# Sheet2-bms.net
KiCad netlist of a schematic drawn in Altium Designer
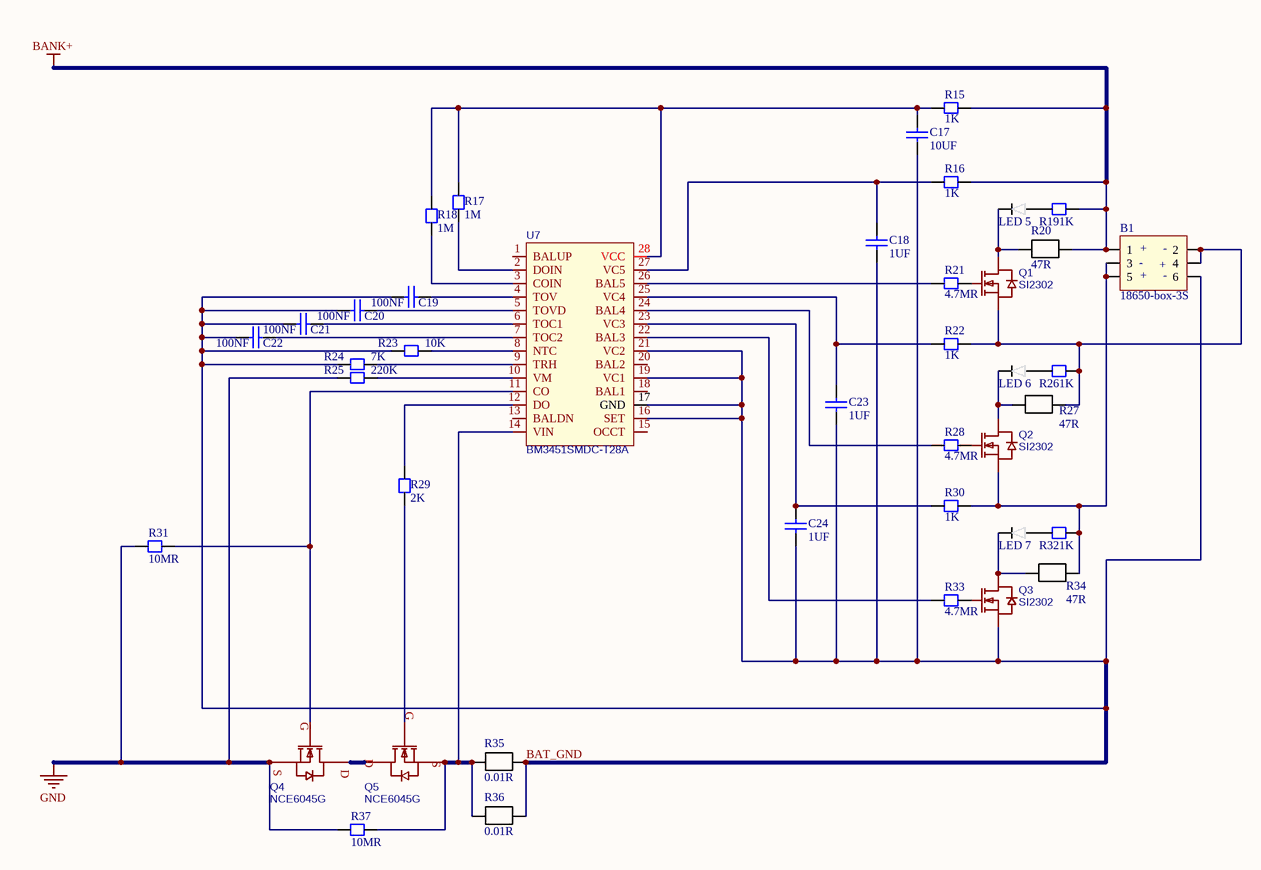
[diagram p0: Sheet2-bms.SchDoc]

(export (version "E")
  (design (tool "Eeschema 10.0.6"))
  (components
    (comp (ref "B1")
      (value "18650-box-3S")
      (footprint "BAT-SMD_BH-18650-B5BA016")
      (description "18650贴片电池盒")
      (libsource (lib "power-chip") (part "18650-box-3S"))
    )
    (comp (ref "C17")
      (value "10UF")
      (footprint "CC1608-0603")
      (description "0603封装的电容")
      (fields (field (name "PUBLISHER") "Altium Limited"))
      (libsource (lib "base") (part "Cap Chip 0603"))
    )
    (comp (ref "C18")
      (value "1UF")
      (footprint "CC1608-0603")
      (description "0603封装的电容")
      (fields (field (name "PUBLISHER") "Altium Limited"))
      (libsource (lib "base") (part "Cap Chip 0603"))
    )
    (comp (ref "C19")
      (value "100NF")
      (footprint "CC1608-0603")
      (description "0603封装的电容")
      (fields (field (name "PUBLISHER") "Altium Limited"))
      (libsource (lib "base") (part "Cap Chip 0603"))
    )
    (comp (ref "C20")
      (value "100NF")
      (footprint "CC1608-0603")
      (description "0603封装的电容")
      (fields (field (name "PUBLISHER") "Altium Limited"))
      (libsource (lib "base") (part "Cap Chip 0603"))
    )
    (comp (ref "C21")
      (value "100NF")
      (footprint "CC1608-0603")
      (description "0603封装的电容")
      (fields (field (name "PUBLISHER") "Altium Limited"))
      (libsource (lib "base") (part "Cap Chip 0603"))
    )
    (comp (ref "C22")
      (value "100NF")
      (footprint "CC1608-0603")
      (description "0603封装的电容")
      (fields (field (name "PUBLISHER") "Altium Limited"))
      (libsource (lib "base") (part "Cap Chip 0603"))
    )
    (comp (ref "C23")
      (value "1UF")
      (footprint "CC1608-0603")
      (description "0603封装的电容")
      (fields (field (name "PUBLISHER") "Altium Limited"))
      (libsource (lib "base") (part "Cap Chip 0603"))
    )
    (comp (ref "C24")
      (value "1UF")
      (footprint "CC1608-0603")
      (description "0603封装的电容")
      (fields (field (name "PUBLISHER") "Altium Limited"))
      (libsource (lib "base") (part "Cap Chip 0603"))
    )
    (comp (ref "LED 5") (value "LED 0603") (footprint "LED 0603") (libsource (lib "base") (part "LED 0603")))
    (comp (ref "LED 6") (value "LED 0603") (footprint "LED 0603") (libsource (lib "base") (part "LED 0603")))
    (comp (ref "LED 7") (value "LED 0603") (footprint "LED 0603") (libsource (lib "base") (part "LED 0603")))
    (comp (ref "Q1")
      (value "SI2302")
      (footprint "SOT-23")
      (fields
        (field (name "MANUFACTURER") "TWGMC(台湾迪嘉)")
        (field (name "MANUFACTURER PART") "SI2306")
        (field (name "CONTRIBUTOR") "LCSC")
      )
      (libsource (lib "transistor") (part "SI2302"))
    )
    (comp (ref "Q2")
      (value "SI2302")
      (footprint "SOT-23")
      (fields
        (field (name "MANUFACTURER") "TWGMC(台湾迪嘉)")
        (field (name "MANUFACTURER PART") "SI2306")
        (field (name "CONTRIBUTOR") "LCSC")
      )
      (libsource (lib "transistor") (part "SI2302"))
    )
    (comp (ref "Q3")
      (value "SI2302")
      (footprint "SOT-23")
      (fields
        (field (name "MANUFACTURER") "TWGMC(台湾迪嘉)")
        (field (name "MANUFACTURER PART") "SI2306")
        (field (name "CONTRIBUTOR") "LCSC")
      )
      (libsource (lib "transistor") (part "SI2302"))
    )
    (comp (ref "Q4")
      (value "NCE6045G")
      (footprint "DFN-8_L5.8-W4.9-P1.27-LS6.1-BL-2")
      (description "原装NCE6045G DFN-8(5x6) N沟道60V 45A增强型功率MOSFET场效应管")
      (fields
        (field (name "MANUFACTURER") "TWGMC(台湾迪嘉)")
        (field (name "MANUFACTURER PART") "SI2306")
        (field (name "CONTRIBUTOR") "LCSC")
      )
      (libsource (lib "transistor") (part "NCE6045G"))
    )
    (comp (ref "Q5")
      (value "NCE6045G")
      (footprint "DFN-8_L5.8-W4.9-P1.27-LS6.1-BL-2")
      (description "原装NCE6045G DFN-8(5x6) N沟道60V 45A增强型功率MOSFET场效应管")
      (fields
        (field (name "MANUFACTURER") "TWGMC(台湾迪嘉)")
        (field (name "MANUFACTURER PART") "SI2306")
        (field (name "CONTRIBUTOR") "LCSC")
      )
      (libsource (lib "transistor") (part "NCE6045G"))
    )
    (comp (ref "R15")
      (value "1K")
      (footprint "CR1608-0603")
      (description "0603封装电阻")
      (fields (field (name "PUBLISHER") "Altium Limited"))
      (libsource (lib "") (part "Resistor Chip 0603_1"))
    )
    (comp (ref "R16")
      (value "1K")
      (footprint "CR1608-0603")
      (description "0603封装电阻")
      (fields (field (name "PUBLISHER") "Altium Limited"))
      (libsource (lib "") (part "Resistor Chip 0603_1"))
    )
    (comp (ref "R17")
      (value "1M")
      (footprint "CR1608-0603")
      (description "0603封装电阻")
      (fields (field (name "PUBLISHER") "Altium Limited"))
      (libsource (lib "") (part "Resistor Chip 0603_2"))
    )
    (comp (ref "R18")
      (value "1M")
      (footprint "CR1608-0603")
      (description "0603封装电阻")
      (fields (field (name "PUBLISHER") "Altium Limited"))
      (libsource (lib "") (part "Resistor Chip 0603_2"))
    )
    (comp (ref "R19")
      (value "1K")
      (footprint "CR1608-0603")
      (description "0603封装电阻")
      (fields (field (name "PUBLISHER") "Altium Limited"))
      (libsource (lib "") (part "Resistor Chip 0603_1"))
    )
    (comp (ref "R20")
      (value "47R")
      (footprint "Cap Chip 2512")
      (libsource (lib "base") (part "Cap Chip 2512"))
    )
    (comp (ref "R21")
      (value "4.7MR")
      (footprint "CR1608-0603")
      (description "0603封装电阻")
      (fields (field (name "PUBLISHER") "Altium Limited"))
      (libsource (lib "") (part "Resistor Chip 0603_1"))
    )
    (comp (ref "R22")
      (value "1K")
      (footprint "CR1608-0603")
      (description "0603封装电阻")
      (fields (field (name "PUBLISHER") "Altium Limited"))
      (libsource (lib "") (part "Resistor Chip 0603_1"))
    )
    (comp (ref "R23")
      (value "10K")
      (footprint "CR1608-0603")
      (description "0603封装电阻")
      (fields (field (name "PUBLISHER") "Altium Limited"))
      (libsource (lib "base") (part "Resistor Chip 0603"))
    )
    (comp (ref "R24")
      (value "7K")
      (footprint "CR1608-0603")
      (description "0603封装电阻")
      (fields (field (name "PUBLISHER") "Altium Limited"))
      (libsource (lib "base") (part "Resistor Chip 0603"))
    )
    (comp (ref "R25")
      (value "220K")
      (footprint "CR1608-0603")
      (description "0603封装电阻")
      (fields (field (name "PUBLISHER") "Altium Limited"))
      (libsource (lib "base") (part "Resistor Chip 0603"))
    )
    (comp (ref "R26")
      (value "1K")
      (footprint "CR1608-0603")
      (description "0603封装电阻")
      (fields (field (name "PUBLISHER") "Altium Limited"))
      (libsource (lib "") (part "Resistor Chip 0603_1"))
    )
    (comp (ref "R27")
      (value "47R")
      (footprint "Cap Chip 2512")
      (libsource (lib "base") (part "Cap Chip 2512"))
    )
    (comp (ref "R28")
      (value "4.7MR")
      (footprint "CR1608-0603")
      (description "0603封装电阻")
      (fields (field (name "PUBLISHER") "Altium Limited"))
      (libsource (lib "") (part "Resistor Chip 0603_1"))
    )
    (comp (ref "R29")
      (value "2K")
      (footprint "CR1608-0603")
      (description "0603封装电阻")
      (fields (field (name "PUBLISHER") "Altium Limited"))
      (libsource (lib "") (part "Resistor Chip 0603_2"))
    )
    (comp (ref "R30")
      (value "1K")
      (footprint "CR1608-0603")
      (description "0603封装电阻")
      (fields (field (name "PUBLISHER") "Altium Limited"))
      (libsource (lib "") (part "Resistor Chip 0603_1"))
    )
    (comp (ref "R31")
      (value "10MR")
      (footprint "CR1608-0603")
      (description "0603封装电阻")
      (fields (field (name "PUBLISHER") "Altium Limited"))
      (libsource (lib "") (part "Resistor Chip 0603_1"))
    )
    (comp (ref "R32")
      (value "1K")
      (footprint "CR1608-0603")
      (description "0603封装电阻")
      (fields (field (name "PUBLISHER") "Altium Limited"))
      (libsource (lib "") (part "Resistor Chip 0603_1"))
    )
    (comp (ref "R33")
      (value "4.7MR")
      (footprint "CR1608-0603")
      (description "0603封装电阻")
      (fields (field (name "PUBLISHER") "Altium Limited"))
      (libsource (lib "") (part "Resistor Chip 0603_1"))
    )
    (comp (ref "R34")
      (value "47R")
      (footprint "Cap Chip 2512")
      (libsource (lib "base") (part "Cap Chip 2512"))
    )
    (comp (ref "R35")
      (value "0.01R")
      (footprint "Cap Chip 2512")
      (libsource (lib "base") (part "Cap Chip 2512"))
    )
    (comp (ref "R36")
      (value "0.01R")
      (footprint "Cap Chip 2512")
      (libsource (lib "base") (part "Cap Chip 2512"))
    )
    (comp (ref "R37")
      (value "10MR")
      (footprint "CR1608-0603")
      (description "0603封装电阻")
      (fields (field (name "PUBLISHER") "Altium Limited"))
      (libsource (lib "base") (part "Resistor Chip 0603"))
    )
    (comp (ref "U7")
      (value "BM3451SMDC-T28A")
      (footprint "TSSOP-28")
      (fields (field (name "CONTRIBUTOR") "lcsc"))
      (libsource (lib "power-chip") (part "BM3451SMDC-T28A"))
    )
  )
  (nets
    (net (code "1") (name "/BAT_GND") (class "Default")
      (node (ref "B1") (pin "6") (pinfunction "6_6") (pintype "passive"))
      (node (ref "C17") (pin "1") (pinfunction "1_1") (pintype "passive"))
      (node (ref "C18") (pin "1") (pinfunction "1_1") (pintype "passive"))
      (node (ref "C19") (pin "2") (pinfunction "2_2") (pintype "passive"))
      (node (ref "C20") (pin "2") (pinfunction "2_2") (pintype "passive"))
      (node (ref "C21") (pin "2") (pinfunction "2_2") (pintype "passive"))
      (node (ref "C22") (pin "2") (pinfunction "2_2") (pintype "passive"))
      (node (ref "C23") (pin "1") (pinfunction "1_1") (pintype "passive"))
      (node (ref "C24") (pin "1") (pinfunction "1_1") (pintype "passive"))
      (node (ref "Q3") (pin "2") (pinfunction "S_2") (pintype "passive"))
      (node (ref "R23") (pin "2") (pinfunction "2_2") (pintype "passive"))
      (node (ref "R24") (pin "2") (pinfunction "2_2") (pintype "passive"))
      (node (ref "R35") (pin "2") (pinfunction "2_2") (pintype "passive"))
      (node (ref "R36") (pin "2") (pinfunction "2_2") (pintype "passive"))
      (node (ref "U7") (pin "16") (pinfunction "SET_16") (pintype "passive"))
      (node (ref "U7") (pin "17") (pinfunction "GND_17") (pintype "passive"))
      (node (ref "U7") (pin "19") (pinfunction "VC1_19") (pintype "passive"))
      (node (ref "U7") (pin "21") (pinfunction "VC2_21") (pintype "passive"))
    )
    (net (code "2") (name "BANK+") (class "Default")
      (node (ref "B1") (pin "1") (pinfunction "1_1") (pintype "passive"))
      (node (ref "R15") (pin "2") (pinfunction "2_2") (pintype "passive"))
      (node (ref "R16") (pin "2") (pinfunction "2_2") (pintype "passive"))
      (node (ref "R19") (pin "2") (pinfunction "2_2") (pintype "passive"))
      (node (ref "R20") (pin "2") (pinfunction "2_2") (pintype "passive"))
    )
    (net (code "3") (name "GND") (class "Default")
      (node (ref "Q4") (pin "2") (pinfunction "S_2") (pintype "passive"))
      (node (ref "R25") (pin "2") (pinfunction "2_2") (pintype "passive"))
      (node (ref "R31") (pin "1") (pinfunction "1_1") (pintype "passive"))
      (node (ref "R37") (pin "2") (pinfunction "2_2") (pintype "passive"))
    )
    (net (code "4") (name "Net-(LED 5-Pad1)") (class "Default")
      (node (ref "LED 5") (pin "1") (pinfunction "1_1") (pintype "passive"))
      (node (ref "R19") (pin "1") (pinfunction "1_1") (pintype "passive"))
    )
    (net (code "5") (name "Net-(LED 6-Pad1)") (class "Default")
      (node (ref "LED 6") (pin "1") (pinfunction "1_1") (pintype "passive"))
      (node (ref "R26") (pin "1") (pinfunction "1_1") (pintype "passive"))
    )
    (net (code "6") (name "Net-(LED 7-Pad1)") (class "Default")
      (node (ref "LED 7") (pin "1") (pinfunction "1_1") (pintype "passive"))
      (node (ref "R32") (pin "1") (pinfunction "1_1") (pintype "passive"))
    )
    (net (code "7") (name "Net-(Q1-D)") (class "Default")
      (node (ref "LED 5") (pin "2") (pinfunction "2_2") (pintype "passive"))
      (node (ref "Q1") (pin "3") (pinfunction "D_3") (pintype "passive"))
      (node (ref "R20") (pin "1") (pinfunction "1_1") (pintype "passive"))
    )
    (net (code "8") (name "Net-(Q1-G)") (class "Default")
      (node (ref "Q1") (pin "1") (pinfunction "G_1") (pintype "passive"))
      (node (ref "R21") (pin "2") (pinfunction "2_2") (pintype "passive"))
    )
    (net (code "9") (name "Net-(Q1-S)") (class "Default")
      (node (ref "B1") (pin "2") (pinfunction "2_2") (pintype "passive"))
      (node (ref "B1") (pin "4") (pinfunction "4_4") (pintype "passive"))
      (node (ref "Q1") (pin "2") (pinfunction "S_2") (pintype "passive"))
      (node (ref "R22") (pin "2") (pinfunction "2_2") (pintype "passive"))
      (node (ref "R26") (pin "2") (pinfunction "2_2") (pintype "passive"))
      (node (ref "R27") (pin "2") (pinfunction "2_2") (pintype "passive"))
    )
    (net (code "10") (name "Net-(Q2-D)") (class "Default")
      (node (ref "LED 6") (pin "2") (pinfunction "2_2") (pintype "passive"))
      (node (ref "Q2") (pin "3") (pinfunction "D_3") (pintype "passive"))
      (node (ref "R27") (pin "1") (pinfunction "1_1") (pintype "passive"))
    )
    (net (code "11") (name "Net-(Q2-G)") (class "Default")
      (node (ref "Q2") (pin "1") (pinfunction "G_1") (pintype "passive"))
      (node (ref "R28") (pin "2") (pinfunction "2_2") (pintype "passive"))
    )
    (net (code "12") (name "Net-(Q2-S)") (class "Default")
      (node (ref "B1") (pin "3") (pinfunction "3_3") (pintype "passive"))
      (node (ref "B1") (pin "5") (pinfunction "5_5") (pintype "passive"))
      (node (ref "Q2") (pin "2") (pinfunction "S_2") (pintype "passive"))
      (node (ref "R30") (pin "2") (pinfunction "2_2") (pintype "passive"))
      (node (ref "R32") (pin "2") (pinfunction "2_2") (pintype "passive"))
      (node (ref "R34") (pin "2") (pinfunction "2_2") (pintype "passive"))
    )
    (net (code "13") (name "Net-(Q3-D)") (class "Default")
      (node (ref "LED 7") (pin "2") (pinfunction "2_2") (pintype "passive"))
      (node (ref "Q3") (pin "3") (pinfunction "D_3") (pintype "passive"))
      (node (ref "R34") (pin "1") (pinfunction "1_1") (pintype "passive"))
    )
    (net (code "14") (name "Net-(Q3-G)") (class "Default")
      (node (ref "Q3") (pin "1") (pinfunction "G_1") (pintype "passive"))
      (node (ref "R33") (pin "2") (pinfunction "2_2") (pintype "passive"))
    )
    (net (code "15") (name "Net-(Q4-D)") (class "Default")
      (node (ref "Q4") (pin "3") (pinfunction "D_3") (pintype "passive"))
      (node (ref "Q5") (pin "3") (pinfunction "D_3") (pintype "passive"))
    )
    (net (code "16") (name "Net-(Q4-G)") (class "Default")
      (node (ref "Q4") (pin "1") (pinfunction "G_1") (pintype "passive"))
      (node (ref "R31") (pin "2") (pinfunction "2_2") (pintype "passive"))
      (node (ref "U7") (pin "11") (pinfunction "CO_11") (pintype "passive"))
    )
    (net (code "17") (name "Net-(Q5-G)") (class "Default")
      (node (ref "Q5") (pin "1") (pinfunction "G_1") (pintype "passive"))
      (node (ref "R29") (pin "1") (pinfunction "1_1") (pintype "passive"))
    )
    (net (code "18") (name "Net-(Q5-S)") (class "Default")
      (node (ref "Q5") (pin "2") (pinfunction "S_2") (pintype "passive"))
      (node (ref "R35") (pin "1") (pinfunction "1_1") (pintype "passive"))
      (node (ref "R36") (pin "1") (pinfunction "1_1") (pintype "passive"))
      (node (ref "R37") (pin "1") (pinfunction "1_1") (pintype "passive"))
      (node (ref "U7") (pin "14") (pinfunction "VIN_14") (pintype "passive"))
    )
    (net (code "19") (name "Net-(U7-BAL3)") (class "Default")
      (node (ref "R33") (pin "1") (pinfunction "1_1") (pintype "passive"))
      (node (ref "U7") (pin "22") (pinfunction "BAL3_22") (pintype "passive"))
    )
    (net (code "20") (name "Net-(U7-BAL4)") (class "Default")
      (node (ref "R28") (pin "1") (pinfunction "1_1") (pintype "passive"))
      (node (ref "U7") (pin "24") (pinfunction "BAL4_24") (pintype "passive"))
    )
    (net (code "21") (name "Net-(U7-BAL5)") (class "Default")
      (node (ref "R21") (pin "1") (pinfunction "1_1") (pintype "passive"))
      (node (ref "U7") (pin "26") (pinfunction "BAL5_26") (pintype "passive"))
    )
    (net (code "22") (name "Net-(U7-COIN)") (class "Default")
      (node (ref "R18") (pin "1") (pinfunction "1_1") (pintype "passive"))
      (node (ref "U7") (pin "3") (pinfunction "COIN_3") (pintype "passive"))
    )
    (net (code "23") (name "Net-(U7-DO)") (class "Default")
      (node (ref "R29") (pin "2") (pinfunction "2_2") (pintype "passive"))
      (node (ref "U7") (pin "12") (pinfunction "DO_12") (pintype "passive"))
    )
    (net (code "24") (name "Net-(U7-DOIN)") (class "Default")
      (node (ref "R17") (pin "1") (pinfunction "1_1") (pintype "passive"))
      (node (ref "U7") (pin "2") (pinfunction "DOIN_2") (pintype "passive"))
    )
    (net (code "25") (name "Net-(U7-NTC)") (class "Default")
      (node (ref "R23") (pin "1") (pinfunction "1_1") (pintype "passive"))
      (node (ref "U7") (pin "8") (pinfunction "NTC_8") (pintype "passive"))
    )
    (net (code "26") (name "Net-(U7-TOC1)") (class "Default")
      (node (ref "C21") (pin "1") (pinfunction "1_1") (pintype "passive"))
      (node (ref "U7") (pin "6") (pinfunction "TOC1_6") (pintype "passive"))
    )
    (net (code "27") (name "Net-(U7-TOC2)") (class "Default")
      (node (ref "C22") (pin "1") (pinfunction "1_1") (pintype "passive"))
      (node (ref "U7") (pin "7") (pinfunction "TOC2_7") (pintype "passive"))
    )
    (net (code "28") (name "Net-(U7-TOV)") (class "Default")
      (node (ref "C19") (pin "1") (pinfunction "1_1") (pintype "passive"))
      (node (ref "U7") (pin "4") (pinfunction "TOV_4") (pintype "passive"))
    )
    (net (code "29") (name "Net-(U7-TOVD)") (class "Default")
      (node (ref "C20") (pin "1") (pinfunction "1_1") (pintype "passive"))
      (node (ref "U7") (pin "5") (pinfunction "TOVD_5") (pintype "passive"))
    )
    (net (code "30") (name "Net-(U7-TRH)") (class "Default")
      (node (ref "R24") (pin "1") (pinfunction "1_1") (pintype "passive"))
      (node (ref "U7") (pin "9") (pinfunction "TRH_9") (pintype "passive"))
    )
    (net (code "31") (name "Net-(U7-VC3)") (class "Default")
      (node (ref "C24") (pin "2") (pinfunction "2_2") (pintype "passive"))
      (node (ref "R30") (pin "1") (pinfunction "1_1") (pintype "passive"))
      (node (ref "U7") (pin "23") (pinfunction "VC3_23") (pintype "passive"))
    )
    (net (code "32") (name "Net-(U7-VC4)") (class "Default")
      (node (ref "C23") (pin "2") (pinfunction "2_2") (pintype "passive"))
      (node (ref "R22") (pin "1") (pinfunction "1_1") (pintype "passive"))
      (node (ref "U7") (pin "25") (pinfunction "VC4_25") (pintype "passive"))
    )
    (net (code "33") (name "Net-(U7-VC5)") (class "Default")
      (node (ref "C18") (pin "2") (pinfunction "2_2") (pintype "passive"))
      (node (ref "R16") (pin "1") (pinfunction "1_1") (pintype "passive"))
      (node (ref "U7") (pin "27") (pinfunction "VC5_27") (pintype "passive"))
    )
    (net (code "34") (name "Net-(U7-VCC)") (class "Default")
      (node (ref "C17") (pin "2") (pinfunction "2_2") (pintype "passive"))
      (node (ref "R15") (pin "1") (pinfunction "1_1") (pintype "passive"))
      (node (ref "R17") (pin "2") (pinfunction "2_2") (pintype "passive"))
      (node (ref "R18") (pin "2") (pinfunction "2_2") (pintype "passive"))
      (node (ref "U7") (pin "28") (pinfunction "VCC_28") (pintype "passive"))
    )
    (net (code "35") (name "Net-(U7-VM)") (class "Default")
      (node (ref "R25") (pin "1") (pinfunction "1_1") (pintype "passive"))
      (node (ref "U7") (pin "10") (pinfunction "VM_10") (pintype "passive"))
    )
    (net (code "36") (name "unconnected-(U7-BAL1-Pad18)") (class "Default")
      (node (ref "U7") (pin "18") (pinfunction "BAL1_18") (pintype "passive"))
    )
    (net (code "37") (name "unconnected-(U7-BAL2-Pad20)") (class "Default")
      (node (ref "U7") (pin "20") (pinfunction "BAL2_20") (pintype "passive"))
    )
    (net (code "38") (name "unconnected-(U7-BALDN-Pad13)") (class "Default")
      (node (ref "U7") (pin "13") (pinfunction "BALDN_13") (pintype "passive"))
    )
    (net (code "39") (name "unconnected-(U7-BALUP-Pad1)") (class "Default")
      (node (ref "U7") (pin "1") (pinfunction "BALUP_1") (pintype "passive"))
    )
    (net (code "40") (name "unconnected-(U7-OCCT-Pad15)") (class "Default")
      (node (ref "U7") (pin "15") (pinfunction "OCCT_15") (pintype "passive"))
    )
  )
)
